# squonk.net
KiCad netlist of a schematic drawn in EAGLE
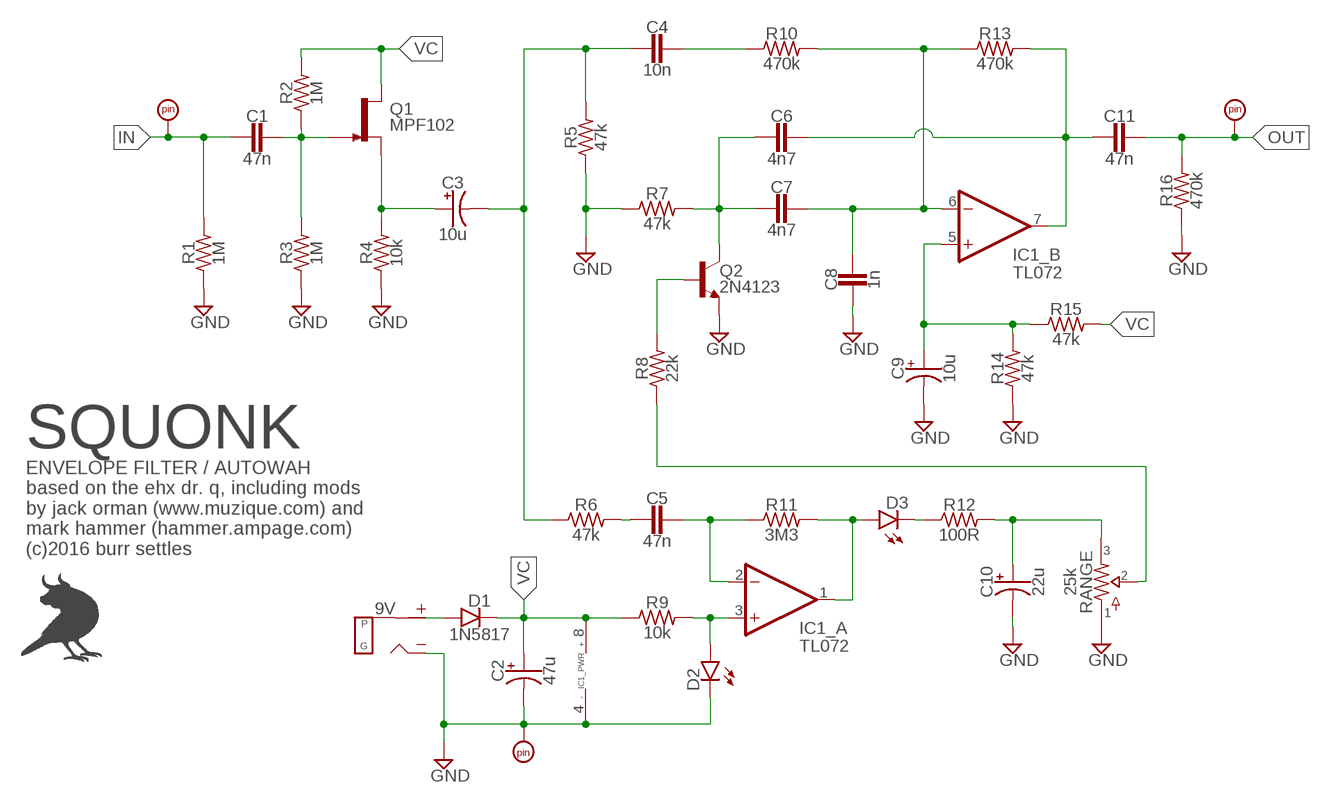
[diagram p0: schematic, sheet 1]

(export (version "E")
  (design (tool "Eeschema 10.0.6"))
  (components
    (comp (ref "9V")
      (value "DC_MONO")
      (footprint "eagle-import:DC")
      (libsource (lib "eagle-import") (part "DC_MONO"))
    )
    (comp (ref "C1")
      (value "47n")
      (footprint "eagle-import:050X030_025_2")
      (libsource (lib "eagle-import") (part "CER/FILM2"))
    )
    (comp (ref "C2")
      (value "47u")
      (footprint "eagle-import:050_020_1")
      (libsource (lib "eagle-import") (part "0501"))
    )
    (comp (ref "C3")
      (value "10u")
      (footprint "eagle-import:050_020_1")
      (libsource (lib "eagle-import") (part "0501"))
    )
    (comp (ref "C4")
      (value "10n")
      (footprint "eagle-import:050X030_025_2")
      (libsource (lib "eagle-import") (part "CER/FILM2"))
    )
    (comp (ref "C5")
      (value "47n")
      (footprint "eagle-import:050X030_025_2")
      (libsource (lib "eagle-import") (part "CER/FILM2"))
    )
    (comp (ref "C6")
      (value "4n7")
      (footprint "eagle-import:050X030_025_2")
      (libsource (lib "eagle-import") (part "CER/FILM2"))
    )
    (comp (ref "C7")
      (value "4n7")
      (footprint "eagle-import:050X030_025_2")
      (libsource (lib "eagle-import") (part "CER/FILM2"))
    )
    (comp (ref "C8")
      (value "1n")
      (footprint "eagle-import:050X030_025_2")
      (libsource (lib "eagle-import") (part "CER/FILM2"))
    )
    (comp (ref "C9")
      (value "10u")
      (footprint "eagle-import:050_020_1")
      (libsource (lib "eagle-import") (part "0501"))
    )
    (comp (ref "C10")
      (value "22u")
      (footprint "eagle-import:050_020_1")
      (libsource (lib "eagle-import") (part "0501"))
    )
    (comp (ref "C11")
      (value "47n")
      (footprint "eagle-import:050X030_025_2")
      (libsource (lib "eagle-import") (part "CER/FILM2"))
    )
    (comp (ref "D1")
      (value "1N5817")
      (footprint "eagle-import:DO41-3")
      (libsource (lib "eagle-import") (part "DO41.3"))
    )
    (comp (ref "D2")
      (value "LEDB")
      (footprint "eagle-import:3MM_B")
      (libsource (lib "eagle-import") (part "LEDB"))
    )
    (comp (ref "D3")
      (value "LEDB")
      (footprint "eagle-import:3MM_B")
      (libsource (lib "eagle-import") (part "LEDB"))
    )
    (comp (ref "GND")
      (value "PADRND")
      (footprint "eagle-import:ROUND")
      (libsource (lib "eagle-import") (part "PADRND"))
    )
    (comp (ref "IC1")
      (value "TL072")
      (footprint "eagle-import:DIL08")
      (libsource (lib "eagle-import") (part "DUALTH"))
    )
    (comp (ref "IN")
      (value "PADSQR")
      (footprint "eagle-import:SQUARE")
      (libsource (lib "eagle-import") (part "PADSQR"))
    )
    (comp (ref "OUT")
      (value "PADSQR")
      (footprint "eagle-import:SQUARE")
      (libsource (lib "eagle-import") (part "PADSQR"))
    )
    (comp (ref "Q1")
      (value "MPF102")
      (footprint "eagle-import:TO92-")
      (libsource (lib "eagle-import") (part "2N5457"))
    )
    (comp (ref "Q2")
      (value "2N4123")
      (footprint "eagle-import:TO92-")
      (libsource (lib "eagle-import") (part "2N3904"))
    )
    (comp (ref "R1")
      (value "1M")
      (footprint "eagle-import:R0207_3")
      (libsource (lib "eagle-import") (part "R_.3B"))
    )
    (comp (ref "R2")
      (value "1M")
      (footprint "eagle-import:R0207_3")
      (libsource (lib "eagle-import") (part "R_.3B"))
    )
    (comp (ref "R3")
      (value "1M")
      (footprint "eagle-import:R0207_3")
      (libsource (lib "eagle-import") (part "R_.3B"))
    )
    (comp (ref "R4")
      (value "10k")
      (footprint "eagle-import:R0207_3")
      (libsource (lib "eagle-import") (part "R_.3B"))
    )
    (comp (ref "R5")
      (value "47k")
      (footprint "eagle-import:R0207_3")
      (libsource (lib "eagle-import") (part "R_.3B"))
    )
    (comp (ref "R6")
      (value "47k")
      (footprint "eagle-import:R0207_3")
      (libsource (lib "eagle-import") (part "R_.3B"))
    )
    (comp (ref "R7")
      (value "47k")
      (footprint "eagle-import:R0207_3")
      (libsource (lib "eagle-import") (part "R_.3B"))
    )
    (comp (ref "R8")
      (value "22k")
      (footprint "eagle-import:R0207_3")
      (libsource (lib "eagle-import") (part "R_.3B"))
    )
    (comp (ref "R9")
      (value "10k")
      (footprint "eagle-import:R0207_3")
      (libsource (lib "eagle-import") (part "R_.3B"))
    )
    (comp (ref "R10")
      (value "470k")
      (footprint "eagle-import:R0207_3")
      (libsource (lib "eagle-import") (part "R_.3B"))
    )
    (comp (ref "R11")
      (value "3M3")
      (footprint "eagle-import:R0207_3")
      (libsource (lib "eagle-import") (part "R_.3B"))
    )
    (comp (ref "R12")
      (value "100R")
      (footprint "eagle-import:R0207_3")
      (libsource (lib "eagle-import") (part "R_.3B"))
    )
    (comp (ref "R13")
      (value "470k")
      (footprint "eagle-import:R0207_3")
      (libsource (lib "eagle-import") (part "R_.3B"))
    )
    (comp (ref "R14")
      (value "47k")
      (footprint "eagle-import:R0207_3")
      (libsource (lib "eagle-import") (part "R_.3B"))
    )
    (comp (ref "R15")
      (value "47k")
      (footprint "eagle-import:R0207_3")
      (libsource (lib "eagle-import") (part "R_.3B"))
    )
    (comp (ref "R16")
      (value "470k")
      (footprint "eagle-import:R0207_3")
      (libsource (lib "eagle-import") (part "R_.3B"))
    )
    (comp (ref "RANGE")
      (value "25k")
      (footprint "eagle-import:PADS_SMALL")
      (libsource (lib "eagle-import") (part "POTSSMALL_PADS"))
    )
  )
  (nets
    (net (code "1") (name "GND") (class "Default")
      (node (ref "9V") (pin "S") (pinfunction "SLEEVE_S") (pintype "passive"))
      (node (ref "C10") (pin "-") (pinfunction "-_-") (pintype "passive"))
      (node (ref "C2") (pin "-") (pinfunction "-_-") (pintype "passive"))
      (node (ref "C8") (pin "2") (pinfunction "2_2") (pintype "passive"))
      (node (ref "C9") (pin "-") (pinfunction "-_-") (pintype "passive"))
      (node (ref "D2") (pin "K") (pinfunction "C_K") (pintype "passive"))
      (node (ref "GND") (pin "1") (pinfunction "P$1_1") (pintype "bidirectional"))
      (node (ref "IC1") (pin "4") (pinfunction "V-_4") (pintype "power_in"))
      (node (ref "Q2") (pin "3") (pinfunction "E_3") (pintype "passive"))
      (node (ref "R1") (pin "1") (pinfunction "1_1") (pintype "passive"))
      (node (ref "R14") (pin "1") (pinfunction "1_1") (pintype "passive"))
      (node (ref "R16") (pin "1") (pinfunction "1_1") (pintype "passive"))
      (node (ref "R3") (pin "1") (pinfunction "1_1") (pintype "passive"))
      (node (ref "R4") (pin "1") (pinfunction "1_1") (pintype "passive"))
      (node (ref "R5") (pin "1") (pinfunction "1_1") (pintype "passive"))
      (node (ref "R7") (pin "1") (pinfunction "1_1") (pintype "passive"))
      (node (ref "RANGE") (pin "1") (pinfunction "1_1") (pintype "passive"))
    )
    (net (code "2") (name "IN") (class "Default")
      (node (ref "C1") (pin "2") (pinfunction "2_2") (pintype "passive"))
      (node (ref "IN") (pin "1") (pinfunction "P$1_1") (pintype "bidirectional"))
      (node (ref "R1") (pin "2") (pinfunction "2_2") (pintype "passive"))
    )
    (net (code "3") (name "Net-(9V-TIP)") (class "Default")
      (node (ref "9V") (pin "T") (pinfunction "TIP_T") (pintype "passive"))
      (node (ref "D1") (pin "A") (pinfunction "A_A") (pintype "passive"))
    )
    (net (code "4") (name "Net-(C3-Pad-)") (class "Default")
      (node (ref "C3") (pin "-") (pinfunction "-_-") (pintype "passive"))
      (node (ref "C4") (pin "2") (pinfunction "2_2") (pintype "passive"))
      (node (ref "R5") (pin "2") (pinfunction "2_2") (pintype "passive"))
      (node (ref "R6") (pin "1") (pinfunction "1_1") (pintype "passive"))
    )
    (net (code "5") (name "Net-(C4-Pad1)") (class "Default")
      (node (ref "C4") (pin "1") (pinfunction "1_1") (pintype "passive"))
      (node (ref "R10") (pin "1") (pinfunction "1_1") (pintype "passive"))
    )
    (net (code "6") (name "Net-(C5-Pad2)") (class "Default")
      (node (ref "C5") (pin "2") (pinfunction "2_2") (pintype "passive"))
      (node (ref "R6") (pin "2") (pinfunction "2_2") (pintype "passive"))
    )
    (net (code "7") (name "Net-(C10-Pad+)") (class "Default")
      (node (ref "C10") (pin "+") (pinfunction "+_+") (pintype "passive"))
      (node (ref "R12") (pin "2") (pinfunction "2_2") (pintype "passive"))
      (node (ref "RANGE") (pin "3") (pinfunction "3_3") (pintype "passive"))
    )
    (net (code "8") (name "Net-(D3-C)") (class "Default")
      (node (ref "D3") (pin "K") (pinfunction "C_K") (pintype "passive"))
      (node (ref "R12") (pin "1") (pinfunction "1_1") (pintype "passive"))
    )
    (net (code "9") (name "Net-(IC1A-+IN)") (class "Default")
      (node (ref "D2") (pin "A") (pinfunction "A_A") (pintype "passive"))
      (node (ref "IC1") (pin "3") (pinfunction "+IN_3") (pintype "input"))
      (node (ref "R9") (pin "2") (pinfunction "2_2") (pintype "passive"))
    )
    (net (code "10") (name "Net-(IC1A--IN)") (class "Default")
      (node (ref "C5") (pin "1") (pinfunction "1_1") (pintype "passive"))
      (node (ref "IC1") (pin "2") (pinfunction "-IN_2") (pintype "input"))
      (node (ref "R11") (pin "1") (pinfunction "1_1") (pintype "passive"))
    )
    (net (code "11") (name "Net-(IC1A-OUT)") (class "Default")
      (node (ref "D3") (pin "A") (pinfunction "A_A") (pintype "passive"))
      (node (ref "IC1") (pin "1") (pinfunction "OUT_1") (pintype "output"))
      (node (ref "R11") (pin "2") (pinfunction "2_2") (pintype "passive"))
    )
    (net (code "12") (name "Net-(IC1B-+IN)") (class "Default")
      (node (ref "C9") (pin "+") (pinfunction "+_+") (pintype "passive"))
      (node (ref "IC1") (pin "5") (pinfunction "+IN_5") (pintype "input"))
      (node (ref "R14") (pin "2") (pinfunction "2_2") (pintype "passive"))
      (node (ref "R15") (pin "1") (pinfunction "1_1") (pintype "passive"))
    )
    (net (code "13") (name "Net-(IC1B--IN)") (class "Default")
      (node (ref "C7") (pin "1") (pinfunction "1_1") (pintype "passive"))
      (node (ref "C8") (pin "1") (pinfunction "1_1") (pintype "passive"))
      (node (ref "IC1") (pin "6") (pinfunction "-IN_6") (pintype "input"))
      (node (ref "R10") (pin "2") (pinfunction "2_2") (pintype "passive"))
      (node (ref "R13") (pin "1") (pinfunction "1_1") (pintype "passive"))
    )
    (net (code "14") (name "Net-(IC1B-OUT)") (class "Default")
      (node (ref "C11") (pin "2") (pinfunction "2_2") (pintype "passive"))
      (node (ref "C6") (pin "1") (pinfunction "1_1") (pintype "passive"))
      (node (ref "IC1") (pin "7") (pinfunction "OUT_7") (pintype "output"))
      (node (ref "R13") (pin "2") (pinfunction "2_2") (pintype "passive"))
    )
    (net (code "15") (name "Net-(Q1-G)") (class "Default")
      (node (ref "C1") (pin "1") (pinfunction "1_1") (pintype "passive"))
      (node (ref "Q1") (pin "1") (pinfunction "G_1") (pintype "passive"))
      (node (ref "R2") (pin "1") (pinfunction "1_1") (pintype "passive"))
      (node (ref "R3") (pin "2") (pinfunction "2_2") (pintype "passive"))
    )
    (net (code "16") (name "Net-(Q1-S)") (class "Default")
      (node (ref "C3") (pin "+") (pinfunction "+_+") (pintype "passive"))
      (node (ref "Q1") (pin "2") (pinfunction "S_2") (pintype "passive"))
      (node (ref "R4") (pin "2") (pinfunction "2_2") (pintype "passive"))
    )
    (net (code "17") (name "Net-(Q2-B)") (class "Default")
      (node (ref "Q2") (pin "2") (pinfunction "B_2") (pintype "passive"))
      (node (ref "R8") (pin "2") (pinfunction "2_2") (pintype "passive"))
    )
    (net (code "18") (name "Net-(Q2-C)") (class "Default")
      (node (ref "C6") (pin "2") (pinfunction "2_2") (pintype "passive"))
      (node (ref "C7") (pin "2") (pinfunction "2_2") (pintype "passive"))
      (node (ref "Q2") (pin "1") (pinfunction "C_1") (pintype "passive"))
      (node (ref "R7") (pin "2") (pinfunction "2_2") (pintype "passive"))
    )
    (net (code "19") (name "Net-(R8-Pad1)") (class "Default")
      (node (ref "R8") (pin "1") (pinfunction "1_1") (pintype "passive"))
      (node (ref "RANGE") (pin "2") (pinfunction "2_2") (pintype "passive"))
    )
    (net (code "20") (name "OUT") (class "Default")
      (node (ref "C11") (pin "1") (pinfunction "1_1") (pintype "passive"))
      (node (ref "OUT") (pin "1") (pinfunction "P$1_1") (pintype "bidirectional"))
      (node (ref "R16") (pin "2") (pinfunction "2_2") (pintype "passive"))
    )
    (net (code "21") (name "VC") (class "Default")
      (node (ref "C2") (pin "+") (pinfunction "+_+") (pintype "passive"))
      (node (ref "D1") (pin "C") (pinfunction "C_C") (pintype "passive"))
      (node (ref "IC1") (pin "8") (pinfunction "V+_8") (pintype "power_in"))
      (node (ref "Q1") (pin "3") (pinfunction "D_3") (pintype "passive"))
      (node (ref "R15") (pin "2") (pinfunction "2_2") (pintype "passive"))
      (node (ref "R2") (pin "2") (pinfunction "2_2") (pintype "passive"))
      (node (ref "R9") (pin "1") (pinfunction "1_1") (pintype "passive"))
    )
  )
)
